# PD_Controller.net
KiCad netlist of a schematic drawn in Altium Designer
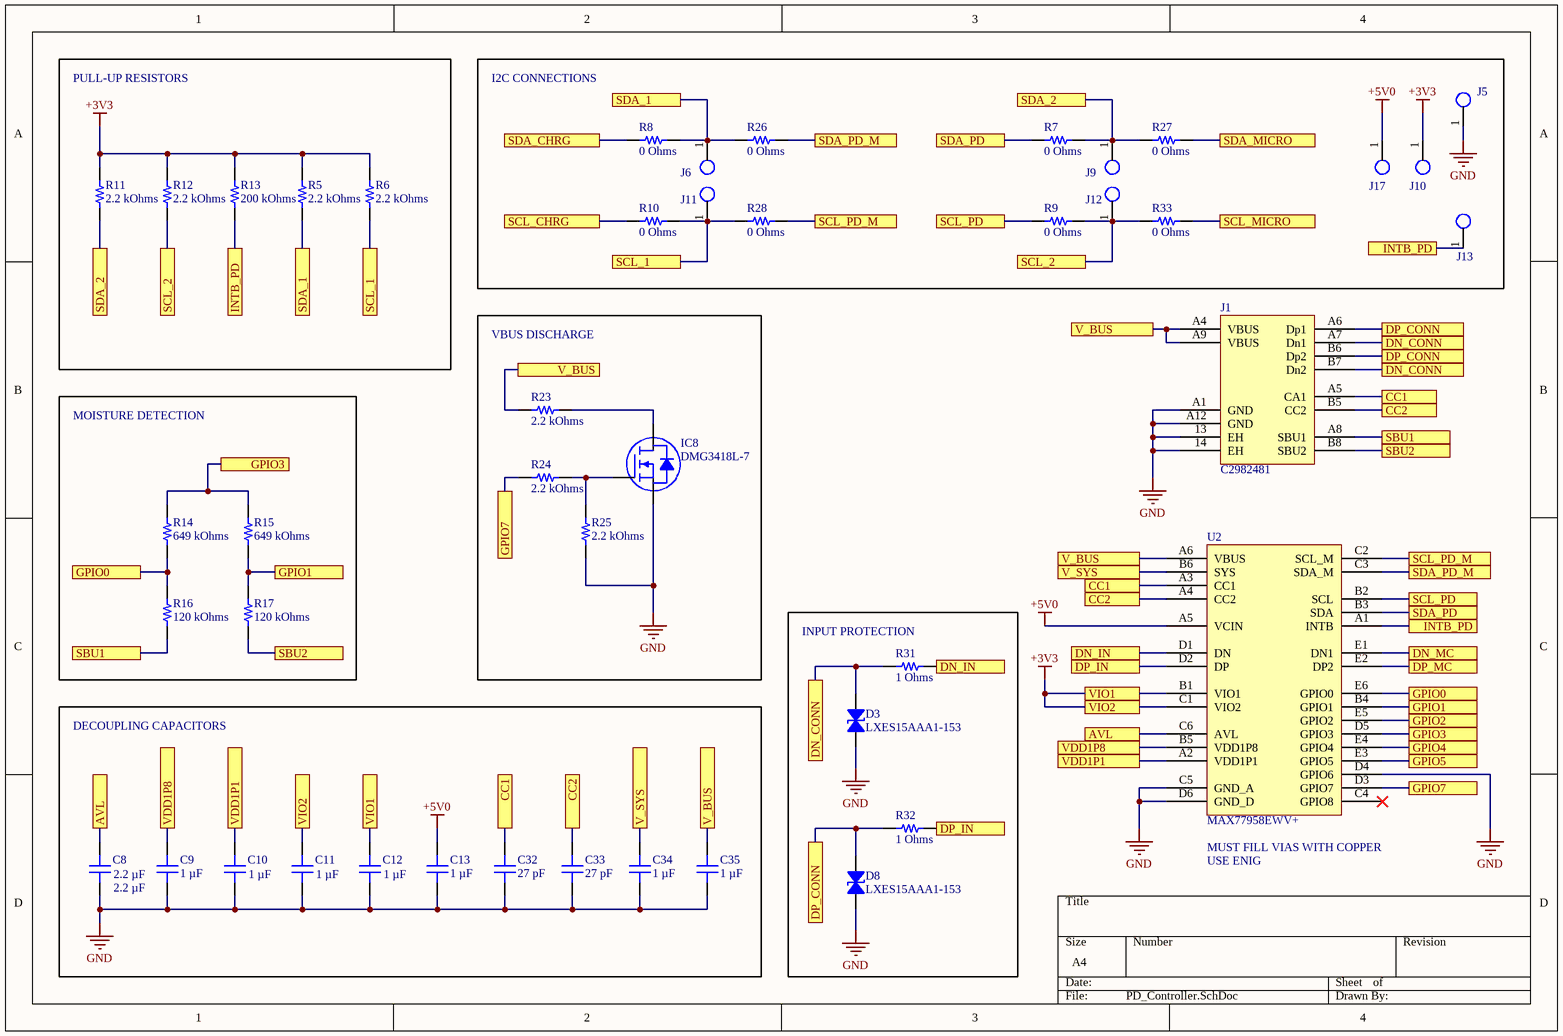
[diagram p0: PD_Controller.SchDoc]

(export (version "E")
  (design (tool "Eeschema 10.0.6"))
  (components
    (comp (ref "C8")
      (value "2.2 µF")
      (footprint "CAP 0402_1005")
      (description "CAP CER 2.2UF 10V X5R 0402")
      (fields
        (field (name "PART NUMBER") "CL05A225KP7NSB8")
        (field (name "ALTIUM_VALUE") "2.2 µF")
        (field (name "MANUFACTURER") "Samsung Electro-Mechanics")
      )
      (libsource (lib "Celestial Altium Library - altium_library") (part "Capacitor"))
    )
    (comp (ref "C9")
      (value "1 µF")
      (footprint "CAP 0402_1005")
      (description "CAP CER 1UF 6.3V X5R 0402")
      (fields (field (name "PART NUMBER") "JMK105BJ105MVHF") (field (name "MANUFACTURER") "Taiyo Yuden"))
      (libsource (lib "Celestial Altium Library - altium_library") (part "Capacitor"))
    )
    (comp (ref "C10")
      (value "1 µF")
      (footprint "CAP 0402_1005")
      (description "CAP CER 1UF 6.3V X5R 0402")
      (fields (field (name "PART NUMBER") "JMK105BJ105MVHF") (field (name "MANUFACTURER") "Taiyo Yuden"))
      (libsource (lib "Celestial Altium Library - altium_library") (part "Capacitor"))
    )
    (comp (ref "C11")
      (value "1 µF")
      (footprint "CAP 0402_1005")
      (description "CAP CER 1UF 6.3V X5R 0402")
      (fields (field (name "PART NUMBER") "JMK105BJ105MVHF") (field (name "MANUFACTURER") "Taiyo Yuden"))
      (libsource (lib "Celestial Altium Library - altium_library") (part "Capacitor"))
    )
    (comp (ref "C12")
      (value "1 µF")
      (footprint "CAP 0402_1005")
      (description "CAP CER 1UF 6.3V X5R 0402")
      (fields (field (name "PART NUMBER") "JMK105BJ105MVHF") (field (name "MANUFACTURER") "Taiyo Yuden"))
      (libsource (lib "Celestial Altium Library - altium_library") (part "Capacitor"))
    )
    (comp (ref "C13")
      (value "1 µF")
      (footprint "CAP 0402_1005")
      (description "CAP CER 1UF 10V X5R 0402")
      (fields (field (name "PART NUMBER") "885012105012") (field (name "MANUFACTURER") "Würth Elektronik"))
      (libsource (lib "Celestial Altium Library - altium_library") (part "Capacitor"))
    )
    (comp (ref "C32")
      (value "27 pF")
      (footprint "CAP 0402_1005")
      (description "CAP CER 27PF 50V C0G/NP0 0402")
      (fields
        (field (name "PART NUMBER") "500R07S270GV4T")
        (field (name "MANUFACTURER") "Johanson Technology Inc.")
      )
      (libsource (lib "Celestial Altium Library - altium_library") (part "Capacitor"))
    )
    (comp (ref "C33")
      (value "27 pF")
      (footprint "CAP 0402_1005")
      (description "CAP CER 27PF 50V C0G/NP0 0402")
      (fields
        (field (name "PART NUMBER") "500R07S270GV4T")
        (field (name "MANUFACTURER") "Johanson Technology Inc.")
      )
      (libsource (lib "Celestial Altium Library - altium_library") (part "Capacitor"))
    )
    (comp (ref "C34")
      (value "1 µF")
      (footprint "CAP 0402_1005")
      (description "CAP CER 1UF 35V X5R 0402")
      (fields
        (field (name "PART NUMBER") "CL05A105KL5NRNC")
        (field (name "MANUFACTURER") "Samsung Electro-Mechanics")
      )
      (libsource (lib "Celestial Altium Library - altium_library") (part "Capacitor"))
    )
    (comp (ref "C35")
      (value "1 µF")
      (footprint "CAP 0402_1005")
      (description "CAP CER 1UF 35V X5R 0402")
      (fields
        (field (name "PART NUMBER") "CL05A105KL5NRNC")
        (field (name "MANUFACTURER") "Samsung Electro-Mechanics")
      )
      (libsource (lib "Celestial Altium Library - altium_library") (part "Capacitor"))
    )
    (comp (ref "D3")
      (value "LXES15AAA1-153")
      (footprint "0402")
      (description "TVS DIODE 4V 1005")
      (fields (field (name "MANUFACTURER") "Murata Electronics"))
      (libsource (lib "Celestial Altium Library - altium_library") (part "Diode TVS"))
    )
    (comp (ref "D8")
      (value "LXES15AAA1-153")
      (footprint "0402")
      (description "TVS DIODE 4V 1005")
      (fields (field (name "MANUFACTURER") "Murata Electronics"))
      (libsource (lib "Celestial Altium Library - altium_library") (part "Diode TVS"))
    )
    (comp (ref "IC8")
      (value "DMG3418L-7")
      (footprint "DIODES SOT-23-3")
      (description "MOSFET N-CH 30V 4A SOT23")
      (fields (field (name "MANUFACTURER") "Diodes Incorporated"))
      (libsource (lib "Celestial Altium Library - altium_library") (part "DIODES INC MOSFET N-CH SOT-23-3"))
    )
    (comp (ref "J1")
      (value "C2982481")
      (footprint "GT-USB-7079A")
      (description "5A 1 Surface Mount 16 Female -55℃~+85℃ Type-C SMD USB Connectors ROHS C2982481")
      (libsource (lib "Schlib2") (part "GT-USB-7079A"))
    )
    (comp (ref "J5")
      (value "Small Board Solder Point")
      (footprint "Small Solder POint")
      (libsource (lib "Schlib2") (part "Small Board Solder Point"))
    )
    (comp (ref "J6")
      (value "Small Board Solder Point")
      (footprint "Small Solder POint")
      (libsource (lib "Schlib2") (part "Small Board Solder Point"))
    )
    (comp (ref "J9")
      (value "Small Board Solder Point")
      (footprint "Small Solder POint")
      (libsource (lib "Schlib2") (part "Small Board Solder Point"))
    )
    (comp (ref "J10")
      (value "Small Board Solder Point")
      (footprint "Small Solder POint")
      (libsource (lib "Schlib2") (part "Small Board Solder Point"))
    )
    (comp (ref "J11")
      (value "Small Board Solder Point")
      (footprint "Small Solder POint")
      (libsource (lib "Schlib2") (part "Small Board Solder Point"))
    )
    (comp (ref "J12")
      (value "Small Board Solder Point")
      (footprint "Small Solder POint")
      (libsource (lib "Schlib2") (part "Small Board Solder Point"))
    )
    (comp (ref "J13")
      (value "Small Board Solder Point")
      (footprint "Small Solder POint")
      (libsource (lib "Schlib2") (part "Small Board Solder Point"))
    )
    (comp (ref "J17")
      (value "Small Board Solder Point")
      (footprint "Small Solder POint")
      (libsource (lib "Schlib2") (part "Small Board Solder Point"))
    )
    (comp (ref "R5")
      (value "2.2 kOhms")
      (footprint "RES 0402_1005")
      (description "RES 2.2K OHM 0.1% 1/10W 0402")
      (fields (field (name "PART NUMBER") "TNPW04022K20BYEP") (field (name "MANUFACTURER") "Vishay Dale"))
      (libsource (lib "Celestial Altium Library - altium_library") (part "Resistor"))
    )
    (comp (ref "R6")
      (value "2.2 kOhms")
      (footprint "RES 0402_1005")
      (description "RES 2.2K OHM 0.1% 1/10W 0402")
      (fields (field (name "PART NUMBER") "TNPW04022K20BYEP") (field (name "MANUFACTURER") "Vishay Dale"))
      (libsource (lib "Celestial Altium Library - altium_library") (part "Resistor"))
    )
    (comp (ref "R7")
      (value "0 Ohms")
      (footprint "RES 0603_1608")
      (description "RES 0 OHM JUMPER 0603")
      (fields
        (field (name "PART NUMBER") "RK73Z1JTTD")
        (field (name "MANUFACTURER") "KOA Speer Electronics, Inc.")
      )
      (libsource (lib "Celestial Altium Library - altium_library") (part "Resistor"))
    )
    (comp (ref "R8")
      (value "0 Ohms")
      (footprint "RES 0603_1608")
      (description "RES 0 OHM JUMPER 0603")
      (fields
        (field (name "PART NUMBER") "RK73Z1JTTD")
        (field (name "MANUFACTURER") "KOA Speer Electronics, Inc.")
      )
      (libsource (lib "Celestial Altium Library - altium_library") (part "Resistor"))
    )
    (comp (ref "R9")
      (value "0 Ohms")
      (footprint "RES 0603_1608")
      (description "RES 0 OHM JUMPER 0603")
      (fields
        (field (name "PART NUMBER") "RK73Z1JTTD")
        (field (name "MANUFACTURER") "KOA Speer Electronics, Inc.")
      )
      (libsource (lib "Celestial Altium Library - altium_library") (part "Resistor"))
    )
    (comp (ref "R10")
      (value "0 Ohms")
      (footprint "RES 0603_1608")
      (description "RES 0 OHM JUMPER 0603")
      (fields
        (field (name "PART NUMBER") "RK73Z1JTTD")
        (field (name "MANUFACTURER") "KOA Speer Electronics, Inc.")
      )
      (libsource (lib "Celestial Altium Library - altium_library") (part "Resistor"))
    )
    (comp (ref "R11")
      (value "2.2 kOhms")
      (footprint "RES 0402_1005")
      (description "RES 2.2K OHM 0.1% 1/10W 0402")
      (fields (field (name "PART NUMBER") "TNPW04022K20BYEP") (field (name "MANUFACTURER") "Vishay Dale"))
      (libsource (lib "Celestial Altium Library - altium_library") (part "Resistor"))
    )
    (comp (ref "R12")
      (value "2.2 kOhms")
      (footprint "RES 0402_1005")
      (description "RES 2.2K OHM 0.1% 1/10W 0402")
      (fields (field (name "PART NUMBER") "TNPW04022K20BYEP") (field (name "MANUFACTURER") "Vishay Dale"))
      (libsource (lib "Celestial Altium Library - altium_library") (part "Resistor"))
    )
    (comp (ref "R13")
      (value "200 kOhms")
      (footprint "RES 0402_1005")
      (description "RES 200K OHM 0.1% 1/10W 0402")
      (fields
        (field (name "PART NUMBER") "RP73PF1E200KBTD")
        (field (name "MANUFACTURER") "TE Connectivity Passive Product")
      )
      (libsource (lib "Celestial Altium Library - altium_library") (part "Resistor"))
    )
    (comp (ref "R14")
      (value "649 kOhms")
      (footprint "RES 0402_1005")
      (description "RES 649K OHM 1% 1/16W 0402")
      (fields
        (field (name "PART NUMBER") "RMCF0402FT649K")
        (field (name "MANUFACTURER") "Stackpole Electronics Inc")
      )
      (libsource (lib "Celestial Altium Library - altium_library") (part "Resistor"))
    )
    (comp (ref "R15")
      (value "649 kOhms")
      (footprint "RES 0402_1005")
      (description "RES 649K OHM 1% 1/16W 0402")
      (fields
        (field (name "PART NUMBER") "RMCF0402FT649K")
        (field (name "MANUFACTURER") "Stackpole Electronics Inc")
      )
      (libsource (lib "Celestial Altium Library - altium_library") (part "Resistor"))
    )
    (comp (ref "R16")
      (value "120 kOhms")
      (footprint "RES 0402_1005")
      (description "RES 120K OHM 1% 1/16W 0402")
      (fields (field (name "PART NUMBER") "RC0402FR-07120KL") (field (name "MANUFACTURER") "Yageo"))
      (libsource (lib "Celestial Altium Library - altium_library") (part "Resistor"))
    )
    (comp (ref "R17")
      (value "120 kOhms")
      (footprint "RES 0402_1005")
      (description "RES 120K OHM 1% 1/16W 0402")
      (fields (field (name "PART NUMBER") "RC0402FR-07120KL") (field (name "MANUFACTURER") "Yageo"))
      (libsource (lib "Celestial Altium Library - altium_library") (part "Resistor"))
    )
    (comp (ref "R23")
      (value "2.2 kOhms")
      (footprint "RES 0805_2012")
      (description "RES SMD 2.2K OHM 5% 1/3W 0805")
      (fields
        (field (name "PART NUMBER") "CRGH0805J2K2")
        (field (name "MANUFACTURER") "TE Connectivity Passive Product")
      )
      (libsource (lib "Celestial Altium Library - altium_library") (part "Resistor"))
    )
    (comp (ref "R24")
      (value "2.2 kOhms")
      (footprint "RES 0402_1005")
      (description "RES 2.2K OHM 0.1% 1/10W 0402")
      (fields (field (name "PART NUMBER") "TNPW04022K20BYEP") (field (name "MANUFACTURER") "Vishay Dale"))
      (libsource (lib "Celestial Altium Library - altium_library") (part "Resistor"))
    )
    (comp (ref "R25")
      (value "2.2 kOhms")
      (footprint "RES 0402_1005")
      (description "RES 2.2K OHM 0.1% 1/10W 0402")
      (fields (field (name "PART NUMBER") "TNPW04022K20BYEP") (field (name "MANUFACTURER") "Vishay Dale"))
      (libsource (lib "Celestial Altium Library - altium_library") (part "Resistor"))
    )
    (comp (ref "R26")
      (value "0 Ohms")
      (footprint "RES 0603_1608")
      (description "RES 0 OHM JUMPER 0603")
      (fields
        (field (name "PART NUMBER") "RK73Z1JTTD")
        (field (name "MANUFACTURER") "KOA Speer Electronics, Inc.")
      )
      (libsource (lib "Celestial Altium Library - altium_library") (part "Resistor"))
    )
    (comp (ref "R27")
      (value "0 Ohms")
      (footprint "RES 0603_1608")
      (description "RES 0 OHM JUMPER 0603")
      (fields
        (field (name "PART NUMBER") "RK73Z1JTTD")
        (field (name "MANUFACTURER") "KOA Speer Electronics, Inc.")
      )
      (libsource (lib "Celestial Altium Library - altium_library") (part "Resistor"))
    )
    (comp (ref "R28")
      (value "0 Ohms")
      (footprint "RES 0603_1608")
      (description "RES 0 OHM JUMPER 0603")
      (fields
        (field (name "PART NUMBER") "RK73Z1JTTD")
        (field (name "MANUFACTURER") "KOA Speer Electronics, Inc.")
      )
      (libsource (lib "Celestial Altium Library - altium_library") (part "Resistor"))
    )
    (comp (ref "R31")
      (value "1 Ohms")
      (footprint "RES 0402_1005")
      (description "RES 1 OHM 5% 1/16W 0402")
      (fields (field (name "PART NUMBER") "RC0402JR-071RL") (field (name "MANUFACTURER") "Yageo"))
      (libsource (lib "Celestial Altium Library - altium_library") (part "Resistor"))
    )
    (comp (ref "R32")
      (value "1 Ohms")
      (footprint "RES 0402_1005")
      (description "RES 1 OHM 5% 1/16W 0402")
      (fields (field (name "PART NUMBER") "RC0402JR-071RL") (field (name "MANUFACTURER") "Yageo"))
      (libsource (lib "Celestial Altium Library - altium_library") (part "Resistor"))
    )
    (comp (ref "R33")
      (value "0 Ohms")
      (footprint "RES 0603_1608")
      (description "RES 0 OHM JUMPER 0603")
      (fields
        (field (name "PART NUMBER") "RK73Z1JTTD")
        (field (name "MANUFACTURER") "KOA Speer Electronics, Inc.")
      )
      (libsource (lib "Celestial Altium Library - altium_library") (part "Resistor"))
    )
    (comp (ref "U2")
      (value "MAX77958EWV+")
      (footprint "BGA30C50P6X5_307X262X64")
      (description "Standalone USB Type-C and USB Power Delivery Controller")
      (libsource (lib "Schlib2") (part "MAX77958EWV+"))
    )
  )
  (nets
    (net (code "1") (name "+3V3") (class "Default")
      (node (ref "C11") (pin "2") (pinfunction "2_2") (pintype "passive"))
      (node (ref "C12") (pin "2") (pinfunction "2_2") (pintype "passive"))
      (node (ref "J10") (pin "1") (pintype "passive"))
      (node (ref "R11") (pin "1") (pinfunction "1_1") (pintype "passive"))
      (node (ref "R12") (pin "1") (pinfunction "1_1") (pintype "passive"))
      (node (ref "R13") (pin "2") (pinfunction "2_2") (pintype "passive"))
      (node (ref "R5") (pin "1") (pinfunction "1_1") (pintype "passive"))
      (node (ref "R6") (pin "1") (pinfunction "1_1") (pintype "passive"))
      (node (ref "U2") (pin "B1") (pinfunction "VIO1_B1") (pintype "passive"))
      (node (ref "U2") (pin "C1") (pinfunction "VIO2_C1") (pintype "passive"))
    )
    (net (code "2") (name "+5V0") (class "Default")
      (node (ref "C13") (pin "2") (pinfunction "2_2") (pintype "passive"))
      (node (ref "J17") (pin "1") (pintype "passive"))
      (node (ref "U2") (pin "A5") (pinfunction "VCIN_A5") (pintype "passive"))
    )
    (net (code "3") (name "/AVL") (class "Default")
      (node (ref "C8") (pin "2") (pinfunction "2_2") (pintype "passive"))
      (node (ref "U2") (pin "C6") (pinfunction "AVL_C6") (pintype "passive"))
    )
    (net (code "4") (name "/CC1") (class "Default")
      (node (ref "C32") (pin "2") (pinfunction "2_2") (pintype "passive"))
      (node (ref "J1") (pin "A5") (pinfunction "CA1_A5") (pintype "passive"))
      (node (ref "U2") (pin "A3") (pinfunction "CC1_A3") (pintype "passive"))
    )
    (net (code "5") (name "/CC2") (class "Default")
      (node (ref "C33") (pin "2") (pinfunction "2_2") (pintype "passive"))
      (node (ref "J1") (pin "B5") (pinfunction "CC2_B5") (pintype "passive"))
      (node (ref "U2") (pin "A4") (pinfunction "CC2_A4") (pintype "passive"))
    )
    (net (code "6") (name "/DN_CONN") (class "Default")
      (node (ref "D3") (pin "1") (pinfunction "1_1") (pintype "passive"))
      (node (ref "J1") (pin "A7") (pinfunction "Dn1_A7") (pintype "passive"))
      (node (ref "J1") (pin "B7") (pinfunction "Dn2_B7") (pintype "passive"))
      (node (ref "R31") (pin "2") (pinfunction "2_2") (pintype "passive"))
    )
    (net (code "7") (name "/DN_IN") (class "Default")
      (node (ref "R31") (pin "1") (pinfunction "1_1") (pintype "passive"))
      (node (ref "U2") (pin "D1") (pinfunction "DN_D1") (pintype "passive"))
    )
    (net (code "8") (name "/DN_MC") (class "Default")
      (node (ref "U2") (pin "E1") (pinfunction "DN1_E1") (pintype "passive"))
    )
    (net (code "9") (name "/DP_CONN") (class "Default")
      (node (ref "D8") (pin "1") (pinfunction "1_1") (pintype "passive"))
      (node (ref "J1") (pin "A6") (pinfunction "Dp1_A6") (pintype "passive"))
      (node (ref "J1") (pin "B6") (pinfunction "Dp2_B6") (pintype "passive"))
      (node (ref "R32") (pin "2") (pinfunction "2_2") (pintype "passive"))
    )
    (net (code "10") (name "/DP_IN") (class "Default")
      (node (ref "R32") (pin "1") (pinfunction "1_1") (pintype "passive"))
      (node (ref "U2") (pin "D2") (pinfunction "DP_D2") (pintype "passive"))
    )
    (net (code "11") (name "/DP_MC") (class "Default")
      (node (ref "U2") (pin "E2") (pinfunction "DP2_E2") (pintype "passive"))
    )
    (net (code "12") (name "/GPIO0") (class "Default")
      (node (ref "R14") (pin "1") (pinfunction "1_1") (pintype "passive"))
      (node (ref "R16") (pin "2") (pinfunction "2_2") (pintype "passive"))
      (node (ref "U2") (pin "E6") (pinfunction "GPIO0_E6") (pintype "passive"))
    )
    (net (code "13") (name "/GPIO1") (class "Default")
      (node (ref "R15") (pin "1") (pinfunction "1_1") (pintype "passive"))
      (node (ref "R17") (pin "2") (pinfunction "2_2") (pintype "passive"))
      (node (ref "U2") (pin "B4") (pinfunction "GPIO1_B4") (pintype "passive"))
    )
    (net (code "14") (name "/GPIO2") (class "Default")
      (node (ref "U2") (pin "E5") (pinfunction "GPIO2_E5") (pintype "passive"))
    )
    (net (code "15") (name "/GPIO3") (class "Default")
      (node (ref "R14") (pin "2") (pinfunction "2_2") (pintype "passive"))
      (node (ref "R15") (pin "2") (pinfunction "2_2") (pintype "passive"))
      (node (ref "U2") (pin "D5") (pinfunction "GPIO3_D5") (pintype "passive"))
    )
    (net (code "16") (name "/GPIO4") (class "Default")
      (node (ref "U2") (pin "E4") (pinfunction "GPIO4_E4") (pintype "passive"))
    )
    (net (code "17") (name "/GPIO5") (class "Default")
      (node (ref "U2") (pin "E3") (pinfunction "GPIO5_E3") (pintype "passive"))
    )
    (net (code "18") (name "/GPIO7") (class "Default")
      (node (ref "R24") (pin "1") (pinfunction "1_1") (pintype "passive"))
      (node (ref "U2") (pin "D3") (pinfunction "GPIO7_D3") (pintype "passive"))
    )
    (net (code "19") (name "/INTB_PD") (class "Default")
      (node (ref "J13") (pin "1") (pintype "passive"))
      (node (ref "R13") (pin "1") (pinfunction "1_1") (pintype "passive"))
      (node (ref "U2") (pin "A1") (pinfunction "INTB_A1") (pintype "passive"))
    )
    (net (code "20") (name "/SBU1") (class "Default")
      (node (ref "J1") (pin "A8") (pinfunction "SBU1_A8") (pintype "passive"))
      (node (ref "R16") (pin "1") (pinfunction "1_1") (pintype "passive"))
    )
    (net (code "21") (name "/SBU2") (class "Default")
      (node (ref "J1") (pin "B8") (pinfunction "SBU2_B8") (pintype "passive"))
      (node (ref "R17") (pin "1") (pinfunction "1_1") (pintype "passive"))
    )
    (net (code "22") (name "/SCL_1") (class "Default")
      (node (ref "J11") (pin "1") (pintype "passive"))
      (node (ref "R10") (pin "2") (pinfunction "2_2") (pintype "passive"))
      (node (ref "R28") (pin "1") (pinfunction "1_1") (pintype "passive"))
      (node (ref "R6") (pin "2") (pinfunction "2_2") (pintype "passive"))
    )
    (net (code "23") (name "/SCL_2") (class "Default")
      (node (ref "J12") (pin "1") (pintype "passive"))
      (node (ref "R12") (pin "2") (pinfunction "2_2") (pintype "passive"))
      (node (ref "R33") (pin "1") (pinfunction "1_1") (pintype "passive"))
      (node (ref "R9") (pin "2") (pinfunction "2_2") (pintype "passive"))
    )
    (net (code "24") (name "/SCL_CHRG") (class "Default")
      (node (ref "R10") (pin "1") (pinfunction "1_1") (pintype "passive"))
    )
    (net (code "25") (name "/SCL_MICRO") (class "Default")
      (node (ref "R33") (pin "2") (pinfunction "2_2") (pintype "passive"))
    )
    (net (code "26") (name "/SCL_PD") (class "Default")
      (node (ref "R9") (pin "1") (pinfunction "1_1") (pintype "passive"))
      (node (ref "U2") (pin "B2") (pinfunction "SCL_B2") (pintype "passive"))
    )
    (net (code "27") (name "/SCL_PD_M") (class "Default")
      (node (ref "R28") (pin "2") (pinfunction "2_2") (pintype "passive"))
      (node (ref "U2") (pin "C2") (pinfunction "SCL_M_C2") (pintype "passive"))
    )
    (net (code "28") (name "/SDA_1") (class "Default")
      (node (ref "J6") (pin "1") (pintype "passive"))
      (node (ref "R26") (pin "1") (pinfunction "1_1") (pintype "passive"))
      (node (ref "R5") (pin "2") (pinfunction "2_2") (pintype "passive"))
      (node (ref "R8") (pin "2") (pinfunction "2_2") (pintype "passive"))
    )
    (net (code "29") (name "/SDA_2") (class "Default")
      (node (ref "J9") (pin "1") (pintype "passive"))
      (node (ref "R11") (pin "2") (pinfunction "2_2") (pintype "passive"))
      (node (ref "R27") (pin "1") (pinfunction "1_1") (pintype "passive"))
      (node (ref "R7") (pin "2") (pinfunction "2_2") (pintype "passive"))
    )
    (net (code "30") (name "/SDA_CHRG") (class "Default")
      (node (ref "R8") (pin "1") (pinfunction "1_1") (pintype "passive"))
    )
    (net (code "31") (name "/SDA_MICRO") (class "Default")
      (node (ref "R27") (pin "2") (pinfunction "2_2") (pintype "passive"))
    )
    (net (code "32") (name "/SDA_PD") (class "Default")
      (node (ref "R7") (pin "1") (pinfunction "1_1") (pintype "passive"))
      (node (ref "U2") (pin "B3") (pinfunction "SDA_B3") (pintype "passive"))
    )
    (net (code "33") (name "/SDA_PD_M") (class "Default")
      (node (ref "R26") (pin "2") (pinfunction "2_2") (pintype "passive"))
      (node (ref "U2") (pin "C3") (pinfunction "SDA_M_C3") (pintype "passive"))
    )
    (net (code "34") (name "/VDD1P1") (class "Default")
      (node (ref "C10") (pin "2") (pinfunction "2_2") (pintype "passive"))
      (node (ref "U2") (pin "A2") (pinfunction "VDD1P1_A2") (pintype "passive"))
    )
    (net (code "35") (name "/VDD1P8") (class "Default")
      (node (ref "C9") (pin "2") (pinfunction "2_2") (pintype "passive"))
      (node (ref "U2") (pin "B5") (pinfunction "VDD1P8_B5") (pintype "passive"))
    )
    (net (code "36") (name "/V_BUS") (class "Default")
      (node (ref "C35") (pin "2") (pinfunction "2_2") (pintype "passive"))
      (node (ref "J1") (pin "A4") (pinfunction "VBUS_A4") (pintype "passive"))
      (node (ref "J1") (pin "A9") (pinfunction "VBUS_A9") (pintype "passive"))
      (node (ref "R23") (pin "1") (pinfunction "1_1") (pintype "passive"))
      (node (ref "U2") (pin "A6") (pinfunction "VBUS_A6") (pintype "passive"))
    )
    (net (code "37") (name "/V_SYS") (class "Default")
      (node (ref "C34") (pin "2") (pinfunction "2_2") (pintype "passive"))
      (node (ref "U2") (pin "B6") (pinfunction "SYS_B6") (pintype "passive"))
    )
    (net (code "38") (name "GND") (class "Default")
      (node (ref "C10") (pin "1") (pinfunction "1_1") (pintype "passive"))
      (node (ref "C11") (pin "1") (pinfunction "1_1") (pintype "passive"))
      (node (ref "C12") (pin "1") (pinfunction "1_1") (pintype "passive"))
      (node (ref "C13") (pin "1") (pinfunction "1_1") (pintype "passive"))
      (node (ref "C32") (pin "1") (pinfunction "1_1") (pintype "passive"))
      (node (ref "C33") (pin "1") (pinfunction "1_1") (pintype "passive"))
      (node (ref "C34") (pin "1") (pinfunction "1_1") (pintype "passive"))
      (node (ref "C35") (pin "1") (pinfunction "1_1") (pintype "passive"))
      (node (ref "C8") (pin "1") (pinfunction "1_1") (pintype "passive"))
      (node (ref "C9") (pin "1") (pinfunction "1_1") (pintype "passive"))
      (node (ref "D3") (pin "2") (pinfunction "2_2") (pintype "passive"))
      (node (ref "D8") (pin "2") (pinfunction "2_2") (pintype "passive"))
      (node (ref "IC8") (pin "2") (pinfunction "S_2") (pintype "passive"))
      (node (ref "J1") (pin "13") (pinfunction "EH_13") (pintype "passive"))
      (node (ref "J1") (pin "14") (pinfunction "EH_14") (pintype "passive"))
      (node (ref "J1") (pin "A1") (pinfunction "GND_A1") (pintype "passive"))
      (node (ref "J1") (pin "A12") (pinfunction "GND_A12") (pintype "passive"))
      (node (ref "J5") (pin "1") (pintype "passive"))
      (node (ref "R25") (pin "1") (pinfunction "1_1") (pintype "passive"))
      (node (ref "U2") (pin "C5") (pinfunction "GND_A_C5") (pintype "passive"))
      (node (ref "U2") (pin "D4") (pinfunction "GPIO6_D4") (pintype "passive"))
      (node (ref "U2") (pin "D6") (pinfunction "GND_D_D6") (pintype "passive"))
    )
    (net (code "39") (name "Net-(IC8-D)") (class "Default")
      (node (ref "IC8") (pin "3") (pinfunction "D_3") (pintype "passive"))
      (node (ref "R23") (pin "2") (pinfunction "2_2") (pintype "passive"))
    )
    (net (code "40") (name "Net-(IC8-G)") (class "Default")
      (node (ref "IC8") (pin "1") (pinfunction "G_1") (pintype "passive"))
      (node (ref "R24") (pin "2") (pinfunction "2_2") (pintype "passive"))
      (node (ref "R25") (pin "2") (pinfunction "2_2") (pintype "passive"))
    )
    (net (code "41") (name "unconnected-(U2-GPIO8-PadC4)") (class "Default")
      (node (ref "U2") (pin "C4") (pinfunction "GPIO8_C4") (pintype "passive+no_connect"))
    )
  )
)
